# ButtonStick.net
KiCad netlist of a schematic drawn in Altium Designer
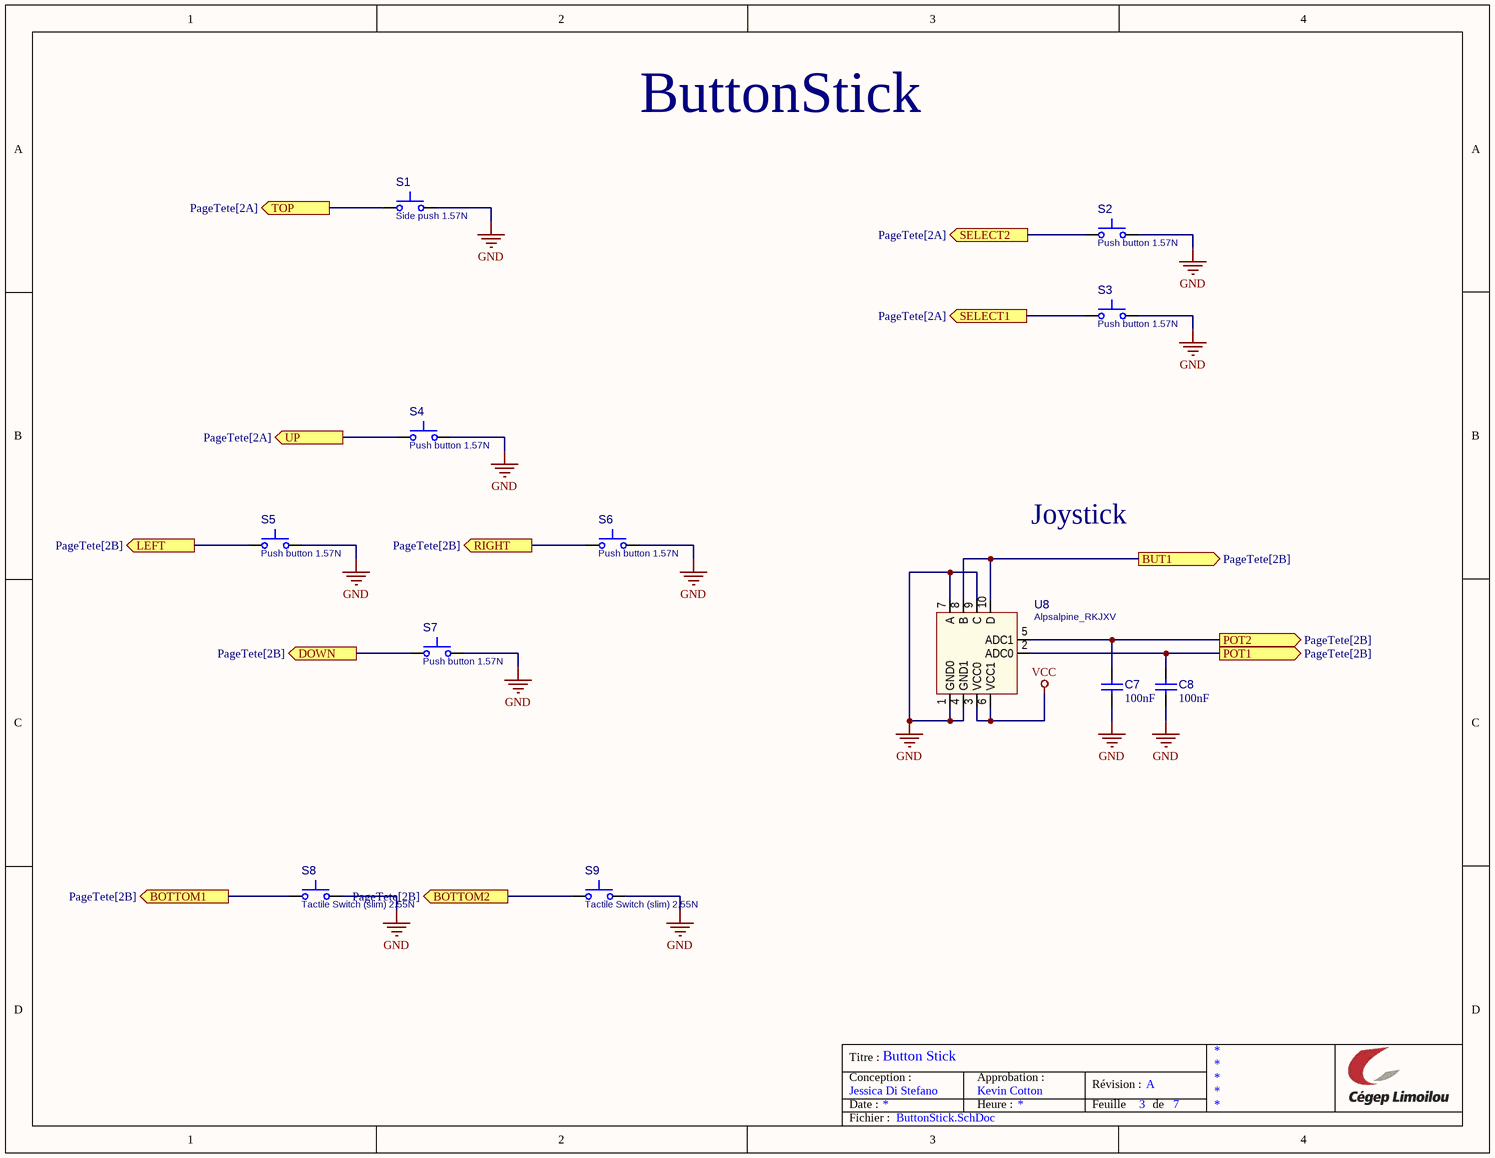
[diagram p0: ButtonStick.SchDoc]

(export (version "E")
  (design (tool "Eeschema 10.0.6"))
  (components
    (comp (ref "C7")
      (value "100nF")
      (footprint "C_1005[0402]")
      (description "Capacitor type 1")
      (fields (field (name "TOLERANCE") "10%") (field (name "Comment") "Cap 100nF 0402"))
      (libsource (lib "TEP_243-Altium_RLC-Lib") (part "CAP001"))
    )
    (comp (ref "C8")
      (value "100nF")
      (footprint "C_1005[0402]")
      (description "Capacitor type 1")
      (fields (field (name "TOLERANCE") "10%") (field (name "Comment") "Cap 100nF 0402"))
      (libsource (lib "TEP_243-Altium_RLC-Lib") (part "CAP001"))
    )
    (comp (ref "S1")
      (value "Side push 1.57N")
      (footprint "S_Alpsalpine_SKHHL")
      (description "Side push 6.0mm Square Type (Snap-in) 1.57N l=3.85mm")
      (fields (field (name "Comment") "SKHHLNA010"))
      (libsource (lib "243-336_MP_Manette_ETU") (part "SW_Push_SKHHL_157N"))
    )
    (comp (ref "S2")
      (value "Push button 1.57N")
      (footprint "S_Alpsalpine_SKPM")
      (fields (field (name "Comment") "SKPMAME010"))
      (libsource (lib "243-336_MP_Manette_ETU") (part "SW_Push_SKPM_157N"))
    )
    (comp (ref "S3")
      (value "Push button 1.57N")
      (footprint "S_Alpsalpine_SKPM")
      (fields (field (name "Comment") "SKPMAME010"))
      (libsource (lib "243-336_MP_Manette_ETU") (part "SW_Push_SKPM_157N"))
    )
    (comp (ref "S4")
      (value "Push button 1.57N")
      (footprint "S_Alpsalpine_SKPM")
      (fields (field (name "Comment") "SKPMAME010"))
      (libsource (lib "243-336_MP_Manette_ETU") (part "SW_Push_SKPM_157N"))
    )
    (comp (ref "S5")
      (value "Push button 1.57N")
      (footprint "S_Alpsalpine_SKPM")
      (fields (field (name "Comment") "SKPMAME010"))
      (libsource (lib "243-336_MP_Manette_ETU") (part "SW_Push_SKPM_157N"))
    )
    (comp (ref "S6")
      (value "Push button 1.57N")
      (footprint "S_Alpsalpine_SKPM")
      (fields (field (name "Comment") "SKPMAME010"))
      (libsource (lib "243-336_MP_Manette_ETU") (part "SW_Push_SKPM_157N"))
    )
    (comp (ref "S7")
      (value "Push button 1.57N")
      (footprint "S_Alpsalpine_SKPM")
      (fields (field (name "Comment") "SKPMAME010"))
      (libsource (lib "243-336_MP_Manette_ETU") (part "SW_Push_SKPM_157N"))
    )
    (comp (ref "S8")
      (value "Tactile Switch (slim) 2.55N")
      (footprint "S_Alpsalpine_SKQG")
      (description "Tactile Switch (dome) 2.55N")
      (fields (field (name "Comment") "SKQGADE010"))
      (libsource (lib "243-336_MP_Manette_ETU") (part "SW_Push_SKQG_255N"))
    )
    (comp (ref "S9")
      (value "Tactile Switch (slim) 2.55N")
      (footprint "S_Alpsalpine_SKQG")
      (description "Tactile Switch (dome) 2.55N")
      (fields (field (name "Comment") "SKQGADE010"))
      (libsource (lib "243-336_MP_Manette_ETU") (part "SW_Push_SKQG_255N"))
    )
    (comp (ref "U8")
      (value "Alpsalpine_RKJXV")
      (footprint "U_Alpsalpine_RKJXV122400R")
      (description "ThumbStick")
      (fields (field (name "Comment") "RKJXV122400R"))
      (libsource (lib "243-336_MP_Manette_ETU") (part "U_Alpsalpine_RKJXV"))
    )
  )
  (nets
    (net (code "1") (name "/BOTTOM1") (class "Default")
      (node (ref "S8") (pin "1") (pinfunction "1_1") (pintype "passive"))
    )
    (net (code "2") (name "/BOTTOM2") (class "Default")
      (node (ref "S9") (pin "1") (pinfunction "1_1") (pintype "passive"))
    )
    (net (code "3") (name "/BUT1") (class "Default")
      (node (ref "U8") (pin "10") (pinfunction "D_10") (pintype "passive"))
      (node (ref "U8") (pin "8") (pinfunction "B_8") (pintype "passive"))
    )
    (net (code "4") (name "/DOWN") (class "Default")
      (node (ref "S7") (pin "1") (pinfunction "1_1") (pintype "passive"))
    )
    (net (code "5") (name "/LEFT") (class "Default")
      (node (ref "S5") (pin "1") (pinfunction "1_1") (pintype "passive"))
    )
    (net (code "6") (name "/POT1") (class "Default")
      (node (ref "C8") (pin "2") (pinfunction "2_2") (pintype "passive"))
      (node (ref "U8") (pin "2") (pinfunction "ADC0_2") (pintype "passive"))
    )
    (net (code "7") (name "/POT2") (class "Default")
      (node (ref "C7") (pin "2") (pinfunction "2_2") (pintype "passive"))
      (node (ref "U8") (pin "5") (pinfunction "ADC1_5") (pintype "passive"))
    )
    (net (code "8") (name "/RIGHT") (class "Default")
      (node (ref "S6") (pin "1") (pinfunction "1_1") (pintype "passive"))
    )
    (net (code "9") (name "/SELECT1") (class "Default")
      (node (ref "S3") (pin "1") (pinfunction "1_1") (pintype "passive"))
    )
    (net (code "10") (name "/SELECT2") (class "Default")
      (node (ref "S2") (pin "1") (pinfunction "1_1") (pintype "passive"))
    )
    (net (code "11") (name "/TOP") (class "Default")
      (node (ref "S1") (pin "1") (pinfunction "1_1") (pintype "passive"))
    )
    (net (code "12") (name "/UP") (class "Default")
      (node (ref "S4") (pin "1") (pinfunction "1_1") (pintype "passive"))
    )
    (net (code "13") (name "GND") (class "Default")
      (node (ref "C7") (pin "1") (pinfunction "1_1") (pintype "passive"))
      (node (ref "C8") (pin "1") (pinfunction "1_1") (pintype "passive"))
      (node (ref "S1") (pin "2") (pinfunction "2_2") (pintype "passive"))
      (node (ref "S2") (pin "2") (pinfunction "2_2") (pintype "passive"))
      (node (ref "S3") (pin "2") (pinfunction "2_2") (pintype "passive"))
      (node (ref "S4") (pin "2") (pinfunction "2_2") (pintype "passive"))
      (node (ref "S5") (pin "2") (pinfunction "2_2") (pintype "passive"))
      (node (ref "S6") (pin "2") (pinfunction "2_2") (pintype "passive"))
      (node (ref "S7") (pin "2") (pinfunction "2_2") (pintype "passive"))
      (node (ref "S8") (pin "2") (pinfunction "2_2") (pintype "passive"))
      (node (ref "S9") (pin "2") (pinfunction "2_2") (pintype "passive"))
      (node (ref "U8") (pin "1") (pinfunction "GND0_1") (pintype "passive"))
      (node (ref "U8") (pin "4") (pinfunction "GND1_4") (pintype "passive"))
      (node (ref "U8") (pin "7") (pinfunction "A_7") (pintype "passive"))
      (node (ref "U8") (pin "9") (pinfunction "C_9") (pintype "passive"))
    )
    (net (code "14") (name "VCC") (class "Default")
      (node (ref "U8") (pin "3") (pinfunction "VCC0_3") (pintype "passive"))
      (node (ref "U8") (pin "6") (pinfunction "VCC1_6") (pintype "passive"))
    )
  )
)
